# breve_E73-2G4M04S.net
KiCad netlist of a schematic drawn in EAGLE
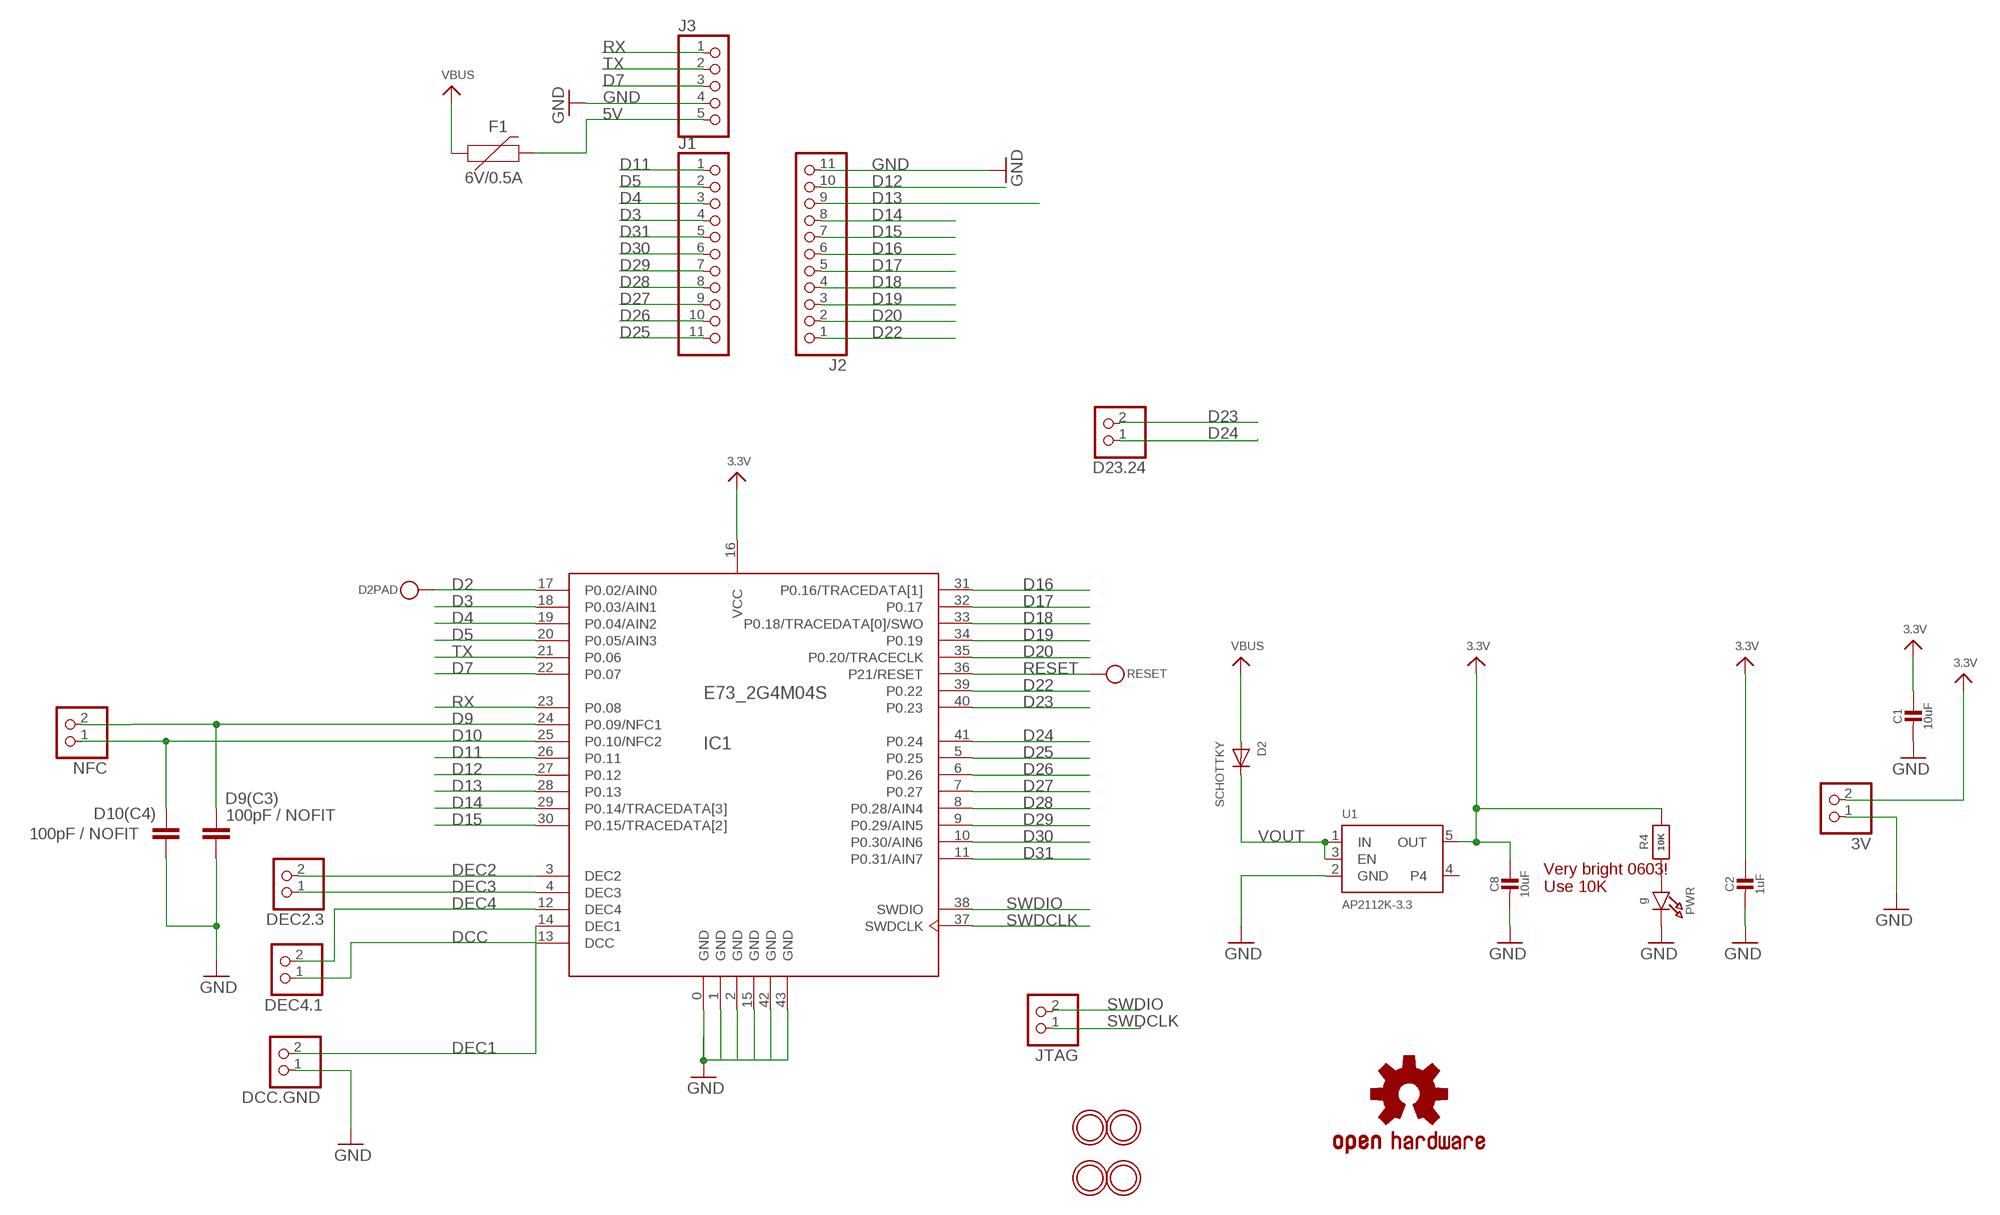
[diagram p0: schematic, sheet 1]

(export (version "E")
  (design (tool "Eeschema 10.0.6"))
  (components
    (comp (ref "3V")
      (value "HEADER-1X2ROUND")
      (footprint "eagle-import:1X02_ROUND")
      (libsource (lib "eagle-import") (part "HEADER-1X2ROUND"))
    )
    (comp (ref "C1")
      (value "10uF")
      (footprint "eagle-import:0805-NO")
      (libsource (lib "eagle-import") (part "CAP_CERAMIC0805-NOOUTLINE"))
    )
    (comp (ref "C2")
      (value "1uF")
      (footprint "eagle-import:0603-NO")
      (libsource (lib "eagle-import") (part "CAP_CERAMIC0603_NO"))
    )
    (comp (ref "C8")
      (value "10uF")
      (footprint "eagle-import:0805-NO")
      (libsource (lib "eagle-import") (part "CAP_CERAMIC0805-NOOUTLINE"))
    )
    (comp (ref "D2")
      (value "SCHOTTKY")
      (footprint "eagle-import:SOD-123FL")
      (libsource (lib "eagle-import") (part "DIODE_SOD-123FL"))
    )
    (comp (ref "D2PAD")
      (value "TESTPOINTROUND1.5MM")
      (footprint "eagle-import:TESTPOINT_ROUND_1.5MM")
      (libsource (lib "eagle-import") (part "TESTPOINTROUND1.5MM"))
    )
    (comp (ref "D9(C3)")
      (value "100pF / NOFIT")
      (footprint "eagle-import:C0603")
      (libsource (lib "eagle-import") (part "C-EUC0603"))
    )
    (comp (ref "D10(C4)")
      (value "100pF / NOFIT")
      (footprint "eagle-import:C0603")
      (libsource (lib "eagle-import") (part "C-EUC0603"))
    )
    (comp (ref "D23.24")
      (value "HEADER-1X2ROUND")
      (footprint "eagle-import:1X02_ROUND")
      (libsource (lib "eagle-import") (part "HEADER-1X2ROUND"))
    )
    (comp (ref "DCC.GND")
      (value "HEADER-1X2ROUND")
      (footprint "eagle-import:1X02_ROUND")
      (libsource (lib "eagle-import") (part "HEADER-1X2ROUND"))
    )
    (comp (ref "DEC2.3")
      (value "HEADER-1X2ROUND")
      (footprint "eagle-import:1X02_ROUND")
      (libsource (lib "eagle-import") (part "HEADER-1X2ROUND"))
    )
    (comp (ref "DEC4.1")
      (value "HEADER-1X2ROUND")
      (footprint "eagle-import:1X02_ROUND")
      (libsource (lib "eagle-import") (part "HEADER-1X2ROUND"))
    )
    (comp (ref "F1")
      (value "6V/0.5A")
      (footprint "eagle-import:1206")
      (libsource (lib "eagle-import") (part "PPTC_HALF-AMP"))
    )
    (comp (ref "IC1")
      (value "E73_2G4M04S")
      (footprint "eagle-import:E73_2G4M04S")
      (libsource (lib "eagle-import") (part "E73_2G4M04S"))
    )
    (comp (ref "J1")
      (value "PINHD-1X11_2.54-SX")
      (footprint "eagle-import:1X11-SX")
      (libsource (lib "eagle-import") (part "PINHD-1X11_2.54-SX"))
    )
    (comp (ref "J2")
      (value "PINHD-1X11_2.54-SX")
      (footprint "eagle-import:1X11-SX")
      (libsource (lib "eagle-import") (part "PINHD-1X11_2.54-SX"))
    )
    (comp (ref "J3")
      (value "PINHD-1X05_2.54-SX")
      (footprint "eagle-import:1X05-SX")
      (libsource (lib "eagle-import") (part "PINHD-1X05_2.54-SX"))
    )
    (comp (ref "JTAG")
      (value "HEADER-1X2ROUND")
      (footprint "eagle-import:1X02_ROUND")
      (libsource (lib "eagle-import") (part "HEADER-1X2ROUND"))
    )
    (comp (ref "LOGO4")
      (value "OSHW-LOGOS")
      (footprint "eagle-import:OSHW-LOGO-S")
      (libsource (lib "eagle-import") (part "OSHW-LOGOS"))
    )
    (comp (ref "NFC")
      (value "HEADER-1X2ROUND")
      (footprint "eagle-import:1X02_ROUND")
      (libsource (lib "eagle-import") (part "HEADER-1X2ROUND"))
    )
    (comp (ref "PWR")
      (value "g")
      (footprint "eagle-import:CHIPLED_0603_NOOUTLINE")
      (libsource (lib "eagle-import") (part "LED0603_NOOUTLINE"))
    )
    (comp (ref "R4")
      (value "10K")
      (footprint "eagle-import:0603-NO")
      (libsource (lib "eagle-import") (part "RESISTOR_0603_NOOUT"))
    )
    (comp (ref "RESET")
      (value "TESTPOINTROUND1.5MM")
      (footprint "eagle-import:TESTPOINT_ROUND_1.5MM")
      (libsource (lib "eagle-import") (part "TESTPOINTROUND1.5MM"))
    )
    (comp (ref "U$2")
      (value "MOUNTINGHOLE2.5")
      (footprint "eagle-import:MOUNTINGHOLE_2.5_PLATED")
      (libsource (lib "eagle-import") (part "MOUNTINGHOLE2.5"))
    )
    (comp (ref "U$6")
      (value "MOUNTINGHOLE2.5")
      (footprint "eagle-import:MOUNTINGHOLE_2.5_PLATED")
      (libsource (lib "eagle-import") (part "MOUNTINGHOLE2.5"))
    )
    (comp (ref "U$31")
      (value "MOUNTINGHOLE2.5")
      (footprint "eagle-import:MOUNTINGHOLE_2.5_PLATED")
      (libsource (lib "eagle-import") (part "MOUNTINGHOLE2.5"))
    )
    (comp (ref "U$32")
      (value "MOUNTINGHOLE2.5")
      (footprint "eagle-import:MOUNTINGHOLE_2.5_PLATED")
      (libsource (lib "eagle-import") (part "MOUNTINGHOLE2.5"))
    )
    (comp (ref "U1")
      (value "AP2112K-3.3")
      (footprint "eagle-import:SOT23-5")
      (libsource (lib "eagle-import") (part "VREG_SOT23-5"))
    )
  )
  (nets
    (net (code "1") (name "/5V") (class "Default")
      (node (ref "F1") (pin "2") (pinfunction "2_2") (pintype "bidirectional"))
      (node (ref "J3") (pin "5") (pinfunction "5_5") (pintype "passive"))
    )
    (net (code "2") (name "/D2") (class "Default")
      (node (ref "D2PAD") (pin "P$1") (pinfunction "P$1_P$1") (pintype "bidirectional"))
      (node (ref "IC1") (pin "17") (pinfunction "P0.02/AIN0_17") (pintype "bidirectional"))
    )
    (net (code "3") (name "/D3") (class "Default")
      (node (ref "IC1") (pin "18") (pinfunction "P0.03/AIN1_18") (pintype "bidirectional"))
      (node (ref "J1") (pin "4") (pinfunction "4_4") (pintype "passive"))
    )
    (net (code "4") (name "/D4") (class "Default")
      (node (ref "IC1") (pin "19") (pinfunction "P0.04/AIN2_19") (pintype "bidirectional"))
      (node (ref "J1") (pin "3") (pinfunction "3_3") (pintype "passive"))
    )
    (net (code "5") (name "/D5") (class "Default")
      (node (ref "IC1") (pin "20") (pinfunction "P0.05/AIN3_20") (pintype "bidirectional"))
      (node (ref "J1") (pin "2") (pinfunction "2_2") (pintype "passive"))
    )
    (net (code "6") (name "/D7") (class "Default")
      (node (ref "IC1") (pin "22") (pinfunction "P0.07_22") (pintype "bidirectional"))
      (node (ref "J3") (pin "3") (pinfunction "3_3") (pintype "passive"))
    )
    (net (code "7") (name "/D9") (class "Default")
      (node (ref "D9(C3)") (pin "2") (pinfunction "2_2") (pintype "passive"))
      (node (ref "IC1") (pin "24") (pinfunction "P0.09/NFC1_24") (pintype "bidirectional"))
      (node (ref "NFC") (pin "2") (pinfunction "2_2") (pintype "passive"))
    )
    (net (code "8") (name "/D10") (class "Default")
      (node (ref "D10(C4)") (pin "2") (pinfunction "2_2") (pintype "passive"))
      (node (ref "IC1") (pin "25") (pinfunction "P0.10/NFC2_25") (pintype "bidirectional"))
      (node (ref "NFC") (pin "1") (pinfunction "1_1") (pintype "passive"))
    )
    (net (code "9") (name "/D11") (class "Default")
      (node (ref "IC1") (pin "26") (pinfunction "P0.11_26") (pintype "bidirectional"))
      (node (ref "J1") (pin "1") (pinfunction "1_1") (pintype "passive"))
    )
    (net (code "10") (name "/D12") (class "Default")
      (node (ref "IC1") (pin "27") (pinfunction "P0.12_27") (pintype "bidirectional"))
      (node (ref "J2") (pin "10") (pinfunction "10_10") (pintype "passive"))
    )
    (net (code "11") (name "/D13") (class "Default")
      (node (ref "IC1") (pin "28") (pinfunction "P0.13_28") (pintype "bidirectional"))
      (node (ref "J2") (pin "9") (pinfunction "9_9") (pintype "passive"))
    )
    (net (code "12") (name "/D14") (class "Default")
      (node (ref "IC1") (pin "29") (pinfunction "P0.14/TRACEDATA[3]_29") (pintype "bidirectional"))
      (node (ref "J2") (pin "8") (pinfunction "8_8") (pintype "passive"))
    )
    (net (code "13") (name "/D15") (class "Default")
      (node (ref "IC1") (pin "30") (pinfunction "P0.15/TRACEDATA[2]_30") (pintype "bidirectional"))
      (node (ref "J2") (pin "7") (pinfunction "7_7") (pintype "passive"))
    )
    (net (code "14") (name "/D16") (class "Default")
      (node (ref "IC1") (pin "31") (pinfunction "P0.16/TRACEDATA[1]_31") (pintype "bidirectional"))
      (node (ref "J2") (pin "6") (pinfunction "6_6") (pintype "passive"))
    )
    (net (code "15") (name "/D17") (class "Default")
      (node (ref "IC1") (pin "32") (pinfunction "P0.17_32") (pintype "bidirectional"))
      (node (ref "J2") (pin "5") (pinfunction "5_5") (pintype "passive"))
    )
    (net (code "16") (name "/D18") (class "Default")
      (node (ref "IC1") (pin "33") (pinfunction "P0.18/TRACEDATA[0]/SWO_33") (pintype "bidirectional"))
      (node (ref "J2") (pin "4") (pinfunction "4_4") (pintype "passive"))
    )
    (net (code "17") (name "/D19") (class "Default")
      (node (ref "IC1") (pin "34") (pinfunction "P0.19_34") (pintype "bidirectional"))
      (node (ref "J2") (pin "3") (pinfunction "3_3") (pintype "passive"))
    )
    (net (code "18") (name "/D20") (class "Default")
      (node (ref "IC1") (pin "35") (pinfunction "P0.20/TRACECLK_35") (pintype "bidirectional"))
      (node (ref "J2") (pin "2") (pinfunction "2_2") (pintype "passive"))
    )
    (net (code "19") (name "/D22") (class "Default")
      (node (ref "IC1") (pin "39") (pinfunction "P0.22_39") (pintype "bidirectional"))
      (node (ref "J2") (pin "1") (pinfunction "1_1") (pintype "passive"))
    )
    (net (code "20") (name "/D23") (class "Default")
      (node (ref "D23.24") (pin "2") (pinfunction "2_2") (pintype "passive"))
      (node (ref "IC1") (pin "40") (pinfunction "P0.23_40") (pintype "bidirectional"))
    )
    (net (code "21") (name "/D24") (class "Default")
      (node (ref "D23.24") (pin "1") (pinfunction "1_1") (pintype "passive"))
      (node (ref "IC1") (pin "41") (pinfunction "P0.24_41") (pintype "bidirectional"))
    )
    (net (code "22") (name "/D25") (class "Default")
      (node (ref "IC1") (pin "5") (pinfunction "P0.25_5") (pintype "bidirectional"))
      (node (ref "J1") (pin "11") (pinfunction "11_11") (pintype "passive"))
    )
    (net (code "23") (name "/D26") (class "Default")
      (node (ref "IC1") (pin "6") (pinfunction "P0.26_6") (pintype "bidirectional"))
      (node (ref "J1") (pin "10") (pinfunction "10_10") (pintype "passive"))
    )
    (net (code "24") (name "/D27") (class "Default")
      (node (ref "IC1") (pin "7") (pinfunction "P0.27_7") (pintype "bidirectional"))
      (node (ref "J1") (pin "9") (pinfunction "9_9") (pintype "passive"))
    )
    (net (code "25") (name "/D28") (class "Default")
      (node (ref "IC1") (pin "8") (pinfunction "P0.28/AIN4_8") (pintype "bidirectional"))
      (node (ref "J1") (pin "8") (pinfunction "8_8") (pintype "passive"))
    )
    (net (code "26") (name "/D29") (class "Default")
      (node (ref "IC1") (pin "9") (pinfunction "P0.29/AIN5_9") (pintype "bidirectional"))
      (node (ref "J1") (pin "7") (pinfunction "7_7") (pintype "passive"))
    )
    (net (code "27") (name "/D30") (class "Default")
      (node (ref "IC1") (pin "10") (pinfunction "P0.30/AIN6_10") (pintype "bidirectional"))
      (node (ref "J1") (pin "6") (pinfunction "6_6") (pintype "passive"))
    )
    (net (code "28") (name "/D31") (class "Default")
      (node (ref "IC1") (pin "11") (pinfunction "P0.31/AIN7_11") (pintype "bidirectional"))
      (node (ref "J1") (pin "5") (pinfunction "5_5") (pintype "passive"))
    )
    (net (code "29") (name "/DCC") (class "Default")
      (node (ref "DEC4.1") (pin "1") (pinfunction "1_1") (pintype "passive"))
      (node (ref "IC1") (pin "13") (pinfunction "DCC_13") (pintype "power_in"))
    )
    (net (code "30") (name "/DEC1") (class "Default")
      (node (ref "DCC.GND") (pin "2") (pinfunction "2_2") (pintype "passive"))
      (node (ref "IC1") (pin "14") (pinfunction "DEC1_14") (pintype "power_in"))
    )
    (net (code "31") (name "/DEC2") (class "Default")
      (node (ref "DEC2.3") (pin "2") (pinfunction "2_2") (pintype "passive"))
      (node (ref "IC1") (pin "3") (pinfunction "DEC2_3") (pintype "power_in"))
    )
    (net (code "32") (name "/DEC3") (class "Default")
      (node (ref "DEC2.3") (pin "1") (pinfunction "1_1") (pintype "passive"))
      (node (ref "IC1") (pin "4") (pinfunction "DEC3_4") (pintype "power_in"))
    )
    (net (code "33") (name "/DEC4") (class "Default")
      (node (ref "DEC4.1") (pin "2") (pinfunction "2_2") (pintype "passive"))
      (node (ref "IC1") (pin "12") (pinfunction "DEC4_12") (pintype "power_in"))
    )
    (net (code "34") (name "/RESET") (class "Default")
      (node (ref "IC1") (pin "36") (pinfunction "P21/RESET_36") (pintype "bidirectional"))
      (node (ref "RESET") (pin "P$1") (pinfunction "P$1_P$1") (pintype "bidirectional"))
    )
    (net (code "35") (name "/RX") (class "Default")
      (node (ref "IC1") (pin "23") (pinfunction "P0.08_23") (pintype "bidirectional"))
      (node (ref "J3") (pin "1") (pinfunction "1_1") (pintype "passive"))
    )
    (net (code "36") (name "/SWDCLK") (class "Default")
      (node (ref "IC1") (pin "37") (pinfunction "SWDCLK_37") (pintype "input"))
      (node (ref "JTAG") (pin "1") (pinfunction "1_1") (pintype "passive"))
    )
    (net (code "37") (name "/SWDIO") (class "Default")
      (node (ref "IC1") (pin "38") (pinfunction "SWDIO_38") (pintype "bidirectional"))
      (node (ref "JTAG") (pin "2") (pinfunction "2_2") (pintype "passive"))
    )
    (net (code "38") (name "/TX") (class "Default")
      (node (ref "IC1") (pin "21") (pinfunction "P0.06_21") (pintype "bidirectional"))
      (node (ref "J3") (pin "2") (pinfunction "2_2") (pintype "passive"))
    )
    (net (code "39") (name "/VOUT") (class "Default")
      (node (ref "D2") (pin "C") (pinfunction "C_C") (pintype "passive"))
      (node (ref "U1") (pin "1") (pinfunction "IN_1") (pintype "power_in"))
      (node (ref "U1") (pin "3") (pinfunction "EN_3") (pintype "input"))
    )
    (net (code "40") (name "3.3V") (class "Default")
      (node (ref "3V") (pin "2") (pinfunction "2_2") (pintype "passive"))
      (node (ref "C1") (pin "1") (pinfunction "1_1") (pintype "passive"))
      (node (ref "C2") (pin "1") (pinfunction "1_1") (pintype "passive"))
      (node (ref "C8") (pin "1") (pinfunction "1_1") (pintype "passive"))
      (node (ref "IC1") (pin "16") (pinfunction "VCC_16") (pintype "passive"))
      (node (ref "R4") (pin "2") (pinfunction "2_2") (pintype "passive"))
      (node (ref "U1") (pin "5") (pinfunction "OUT_5") (pintype "power_in"))
    )
    (net (code "41") (name "GND") (class "Default")
      (node (ref "3V") (pin "1") (pinfunction "1_1") (pintype "passive"))
      (node (ref "C1") (pin "2") (pinfunction "2_2") (pintype "passive"))
      (node (ref "C2") (pin "2") (pinfunction "2_2") (pintype "passive"))
      (node (ref "C8") (pin "2") (pinfunction "2_2") (pintype "passive"))
      (node (ref "D10(C4)") (pin "1") (pinfunction "1_1") (pintype "passive"))
      (node (ref "D9(C3)") (pin "1") (pinfunction "1_1") (pintype "passive"))
      (node (ref "DCC.GND") (pin "1") (pinfunction "1_1") (pintype "passive"))
      (node (ref "IC1") (pin "0") (pinfunction "GND_0") (pintype "bidirectional"))
      (node (ref "IC1") (pin "1") (pinfunction "GND_1") (pintype "bidirectional"))
      (node (ref "IC1") (pin "15") (pinfunction "GND_15") (pintype "bidirectional"))
      (node (ref "IC1") (pin "2") (pinfunction "GND_2") (pintype "bidirectional"))
      (node (ref "IC1") (pin "42") (pinfunction "GND_42") (pintype "bidirectional"))
      (node (ref "IC1") (pin "43") (pinfunction "GND_43") (pintype "bidirectional"))
      (node (ref "J2") (pin "11") (pinfunction "11_11") (pintype "passive"))
      (node (ref "J3") (pin "4") (pinfunction "4_4") (pintype "passive"))
      (node (ref "PWR") (pin "C") (pinfunction "C_C") (pintype "passive"))
      (node (ref "U1") (pin "2") (pinfunction "GND_2") (pintype "power_in"))
    )
    (net (code "42") (name "Net-(PWR-PadA)") (class "Default")
      (node (ref "PWR") (pin "A") (pinfunction "A_A") (pintype "passive"))
      (node (ref "R4") (pin "1") (pinfunction "1_1") (pintype "passive"))
    )
    (net (code "43") (name "VBUS") (class "Default")
      (node (ref "D2") (pin "A") (pinfunction "A_A") (pintype "passive"))
      (node (ref "F1") (pin "1") (pinfunction "1_1") (pintype "bidirectional"))
    )
    (net (code "44") (name "unconnected-(U1-P4-Pad4)") (class "Default")
      (node (ref "U1") (pin "4") (pinfunction "P4_4") (pintype "bidirectional"))
    )
  )
)
